# Att_steet_2.net
KiCad netlist of a schematic drawn in Altium Designer
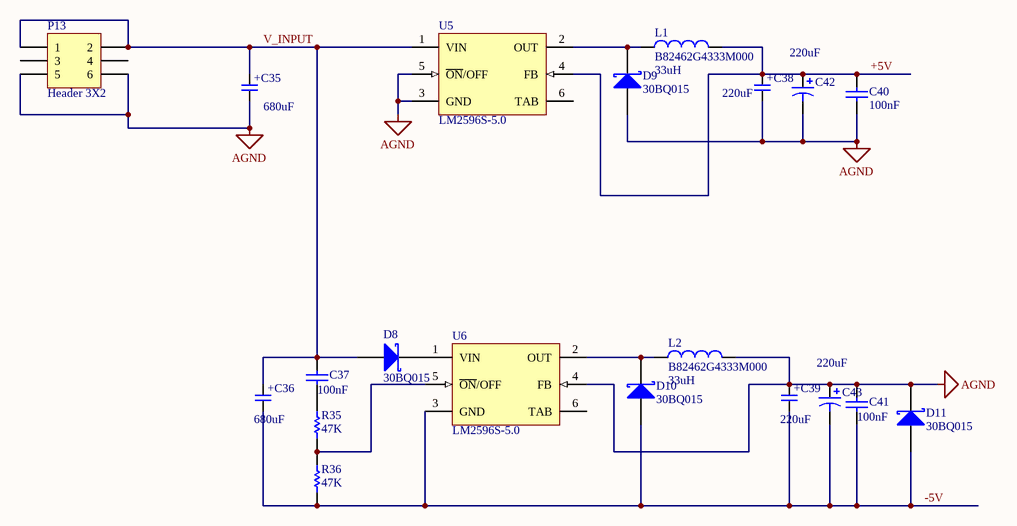
[diagram p0: Att_steet_2.SchDoc]

(export (version "E")
  (design (tool "Eeschema 10.0.6"))
  (components
    (comp (ref "C35")
      (value "680uF")
      (footprint "Scope:H13")
      (fields (field (name "MANUFACTURER") "Panasonic") (field (name "Comment") "Cap"))
      (libsource (lib "Scope") (part "Lyt Cap"))
    )
    (comp (ref "C36")
      (value "680uF")
      (footprint "Scope:H13")
      (fields (field (name "MANUFACTURER") "Panasonic") (field (name "Comment") "Cap"))
      (libsource (lib "Scope") (part "Lyt Cap"))
    )
    (comp (ref "C37")
      (value "100nF")
      (footprint "0805")
      (description "Ceramic Chip Capacitor - Standard")
      (fields (field (name "Comment") "C0805") (field (name "PUBLISHER") "Altium Limited"))
      (libsource (lib "KEMET Chip Capacitor") (part "C0805"))
    )
    (comp (ref "C38")
      (value "220uF")
      (footprint "Scope:H13")
      (fields (field (name "MANUFACTURER") "Panasonic") (field (name "Comment") "Cap"))
      (libsource (lib "Scope") (part "Lyt Cap"))
    )
    (comp (ref "C39")
      (value "220uF")
      (footprint "Scope:H13")
      (fields (field (name "MANUFACTURER") "Panasonic") (field (name "Comment") "Cap"))
      (libsource (lib "Scope") (part "Lyt Cap"))
    )
    (comp (ref "C40")
      (value "100nF")
      (footprint "0805")
      (description "Ceramic Chip Capacitor - Standard")
      (fields (field (name "Comment") "C0805") (field (name "PUBLISHER") "Altium Limited"))
      (libsource (lib "KEMET Chip Capacitor") (part "C0805"))
    )
    (comp (ref "C41")
      (value "100nF")
      (footprint "0805")
      (description "Ceramic Chip Capacitor - Standard")
      (fields (field (name "Comment") "C0805") (field (name "PUBLISHER") "Altium Limited"))
      (libsource (lib "KEMET Chip Capacitor") (part "C0805"))
    )
    (comp (ref "C42")
      (value "220uF")
      (footprint "E")
      (description "Solid Tantalum Chip Capacitor, T510 Series - Ultra-Low ESR")
      (fields (field (name "Comment") "T510E") (field (name "PUBLISHER") "Altium Limited"))
      (libsource (lib "KEMET Chip Capacitor") (part "T510E"))
    )
    (comp (ref "C43")
      (value "220uF")
      (footprint "E")
      (description "Solid Tantalum Chip Capacitor, T510 Series - Ultra-Low ESR")
      (fields (field (name "Comment") "T510E") (field (name "PUBLISHER") "Altium Limited"))
      (libsource (lib "KEMET Chip Capacitor") (part "T510E"))
    )
    (comp (ref "D8")
      (value "30BQ015")
      (footprint "SMC")
      (description "Schottky Rectifier")
      (fields (field (name "PUBLISHER") "Altium Limited"))
      (libsource (lib "IR Rectifier - Schottky") (part "30BQ015"))
    )
    (comp (ref "D9")
      (value "30BQ015")
      (footprint "SMC")
      (description "Schottky Rectifier")
      (fields (field (name "PUBLISHER") "Altium Limited"))
      (libsource (lib "IR Rectifier - Schottky") (part "30BQ015"))
    )
    (comp (ref "D10")
      (value "30BQ015")
      (footprint "SMC")
      (description "Schottky Rectifier")
      (fields (field (name "PUBLISHER") "Altium Limited"))
      (libsource (lib "IR Rectifier - Schottky") (part "30BQ015"))
    )
    (comp (ref "D11")
      (value "30BQ015")
      (footprint "SMC")
      (description "Schottky Rectifier")
      (fields (field (name "PUBLISHER") "Altium Limited"))
      (libsource (lib "IR Rectifier - Schottky") (part "30BQ015"))
    )
    (comp (ref "L1")
      (value "B82462G4333M000")
      (footprint "B82462G4")
      (description "SMT Power Inductor; Size 6.3×6.3×3.0mm, ±20% Tolerance, 33uH, 0.85A")
      (fields (field (name "ALTIUM_VALUE") "33uH") (field (name "PUBLISHER") "Altium Limited"))
      (libsource (lib "EPCOS Inductor") (part "B82462G4333M000"))
    )
    (comp (ref "L2")
      (value "B82462G4333M000")
      (footprint "B82462G4")
      (description "SMT Power Inductor; Size 6.3×6.3×3.0mm, ±20% Tolerance, 33uH, 0.85A")
      (fields (field (name "ALTIUM_VALUE") "33uH") (field (name "PUBLISHER") "Altium Limited"))
      (libsource (lib "EPCOS Inductor") (part "B82462G4333M000"))
    )
    (comp (ref "P13")
      (value "Header 3X2")
      (footprint "HDR2X3")
      (description "Header, 3-Pin, Dual row")
      (fields (field (name "PUBLISHER") "Altium Limited"))
      (libsource (lib "Miscellaneous Connectors") (part "Header 3X2"))
    )
    (comp (ref "R35")
      (value "47K")
      (footprint "0805")
      (fields (field (name "Comment") "ERA6Y") (field (name "PUBLISHER") "Altium Limited"))
      (libsource (lib "Panasonic Resistor") (part "ERA6Y"))
    )
    (comp (ref "R36")
      (value "47K")
      (footprint "0805")
      (fields (field (name "Comment") "ERA6Y") (field (name "PUBLISHER") "Altium Limited"))
      (libsource (lib "Panasonic Resistor") (part "ERA6Y"))
    )
    (comp (ref "U5")
      (value "LM2596S-5.0")
      (footprint "TS5B_N")
      (description "SIMPLE SWITCHER Power Converter 150 KHz 3A Step-Down Voltage Regulator")
      (fields
        (field (name "MANUFACTURER") "National Semiconductor")
        (field (name "DIGIKEYPARTNUMBER") "LM2596S-5.0-ND")
        (field (name "PUBLISHER") "Altium Limited")
      )
      (libsource (lib "NSC Switcher") (part "LM2596S-5.0"))
    )
    (comp (ref "U6")
      (value "LM2596S-5.0")
      (footprint "TS5B_N")
      (description "SIMPLE SWITCHER Power Converter 150 KHz 3A Step-Down Voltage Regulator")
      (fields
        (field (name "MANUFACTURER") "National Semiconductor")
        (field (name "DIGIKEYPARTNUMBER") "LM2596S-5.0-ND")
        (field (name "PUBLISHER") "Altium Limited")
      )
      (libsource (lib "NSC Switcher") (part "LM2596S-5.0"))
    )
  )
  (nets
    (net (code "1") (name "/+5V") (class "Default")
      (node (ref "C38") (pin "1") (pinfunction "1_1") (pintype "passive"))
      (node (ref "C40") (pin "2") (pinfunction "2_2") (pintype "passive"))
      (node (ref "C42") (pin "1") (pinfunction "1_1") (pintype "passive"))
      (node (ref "L1") (pin "2") (pinfunction "2_2") (pintype "passive"))
      (node (ref "U5") (pin "4") (pinfunction "FB_4") (pintype "input"))
    )
    (net (code "2") (name "/-5V") (class "Default")
      (node (ref "C36") (pin "2") (pinfunction "2_2") (pintype "passive"))
      (node (ref "C39") (pin "2") (pinfunction "2_2") (pintype "passive"))
      (node (ref "C41") (pin "1") (pinfunction "1_1") (pintype "passive"))
      (node (ref "C43") (pin "2") (pinfunction "2_2") (pintype "passive"))
      (node (ref "D10") (pin "1") (pinfunction "A_1") (pintype "passive"))
      (node (ref "D11") (pin "1") (pinfunction "A_1") (pintype "passive"))
      (node (ref "R36") (pin "2") (pinfunction "2_2") (pintype "passive"))
      (node (ref "U6") (pin "3") (pinfunction "GND_3") (pintype "power_in"))
    )
    (net (code "3") (name "/V_INPUT") (class "Default")
      (node (ref "C35") (pin "1") (pinfunction "1_1") (pintype "passive"))
      (node (ref "C36") (pin "1") (pinfunction "1_1") (pintype "passive"))
      (node (ref "C37") (pin "2") (pinfunction "2_2") (pintype "passive"))
      (node (ref "D8") (pin "1") (pinfunction "A_1") (pintype "passive"))
      (node (ref "P13") (pin "1") (pinfunction "1_1") (pintype "passive"))
      (node (ref "P13") (pin "2") (pinfunction "2_2") (pintype "passive"))
      (node (ref "U5") (pin "1") (pinfunction "VIN_1") (pintype "power_in"))
    )
    (net (code "4") (name "AGND") (class "Default")
      (node (ref "C35") (pin "2") (pinfunction "2_2") (pintype "passive"))
      (node (ref "C38") (pin "2") (pinfunction "2_2") (pintype "passive"))
      (node (ref "C39") (pin "1") (pinfunction "1_1") (pintype "passive"))
      (node (ref "C40") (pin "1") (pinfunction "1_1") (pintype "passive"))
      (node (ref "C41") (pin "2") (pinfunction "2_2") (pintype "passive"))
      (node (ref "C42") (pin "2") (pinfunction "2_2") (pintype "passive"))
      (node (ref "C43") (pin "1") (pinfunction "1_1") (pintype "passive"))
      (node (ref "D11") (pin "2") (pinfunction "K_2") (pintype "passive"))
      (node (ref "D9") (pin "1") (pinfunction "A_1") (pintype "passive"))
      (node (ref "L2") (pin "2") (pinfunction "2_2") (pintype "passive"))
      (node (ref "P13") (pin "5") (pinfunction "5_5") (pintype "passive"))
      (node (ref "P13") (pin "6") (pinfunction "6_6") (pintype "passive"))
      (node (ref "U5") (pin "3") (pinfunction "GND_3") (pintype "power_in"))
      (node (ref "U5") (pin "5") (pinfunction "~{ON}/OFF_5") (pintype "input"))
      (node (ref "U6") (pin "4") (pinfunction "FB_4") (pintype "input"))
    )
    (net (code "5") (name "Net-(C37-Pad1)") (class "Default")
      (node (ref "C37") (pin "1") (pinfunction "1_1") (pintype "passive"))
      (node (ref "R35") (pin "1") (pinfunction "1_1") (pintype "passive"))
    )
    (net (code "6") (name "Net-(D8-K)") (class "Default")
      (node (ref "D8") (pin "2") (pinfunction "K_2") (pintype "passive"))
      (node (ref "U6") (pin "1") (pinfunction "VIN_1") (pintype "power_in"))
    )
    (net (code "7") (name "Net-(D9-K)") (class "Default")
      (node (ref "D9") (pin "2") (pinfunction "K_2") (pintype "passive"))
      (node (ref "L1") (pin "1") (pinfunction "1_1") (pintype "passive"))
      (node (ref "U5") (pin "2") (pinfunction "OUT_2") (pintype "power_in"))
    )
    (net (code "8") (name "Net-(D10-K)") (class "Default")
      (node (ref "D10") (pin "2") (pinfunction "K_2") (pintype "passive"))
      (node (ref "L2") (pin "1") (pinfunction "1_1") (pintype "passive"))
      (node (ref "U6") (pin "2") (pinfunction "OUT_2") (pintype "power_in"))
    )
    (net (code "9") (name "Net-(U6-~{ON}{slash}OFF)") (class "Default")
      (node (ref "R35") (pin "2") (pinfunction "2_2") (pintype "passive"))
      (node (ref "R36") (pin "1") (pinfunction "1_1") (pintype "passive"))
      (node (ref "U6") (pin "5") (pinfunction "~{ON}/OFF_5") (pintype "input"))
    )
    (net (code "10") (name "unconnected-(P13-Pad3)") (class "Default")
      (node (ref "P13") (pin "3") (pinfunction "3_3") (pintype "passive"))
    )
    (net (code "11") (name "unconnected-(P13-Pad4)") (class "Default")
      (node (ref "P13") (pin "4") (pinfunction "4_4") (pintype "passive"))
    )
    (net (code "12") (name "unconnected-(U5-TAB-Pad6)") (class "Default")
      (node (ref "U5") (pin "6") (pinfunction "TAB_6") (pintype "power_in"))
    )
    (net (code "13") (name "unconnected-(U6-TAB-Pad6)") (class "Default")
      (node (ref "U6") (pin "6") (pinfunction "TAB_6") (pintype "power_in"))
    )
  )
)
